# USB.net
KiCad netlist of a schematic drawn in Altium Designer
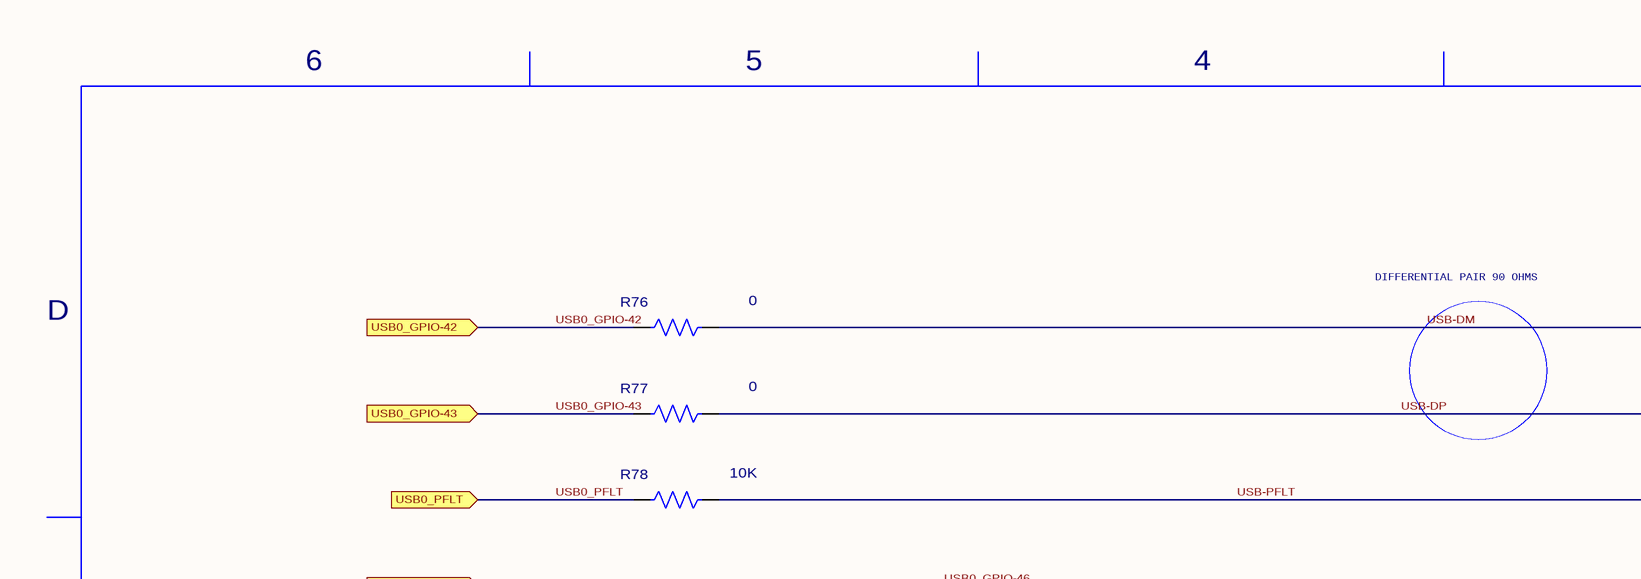
[diagram p0: USB.SchDoc, top left]
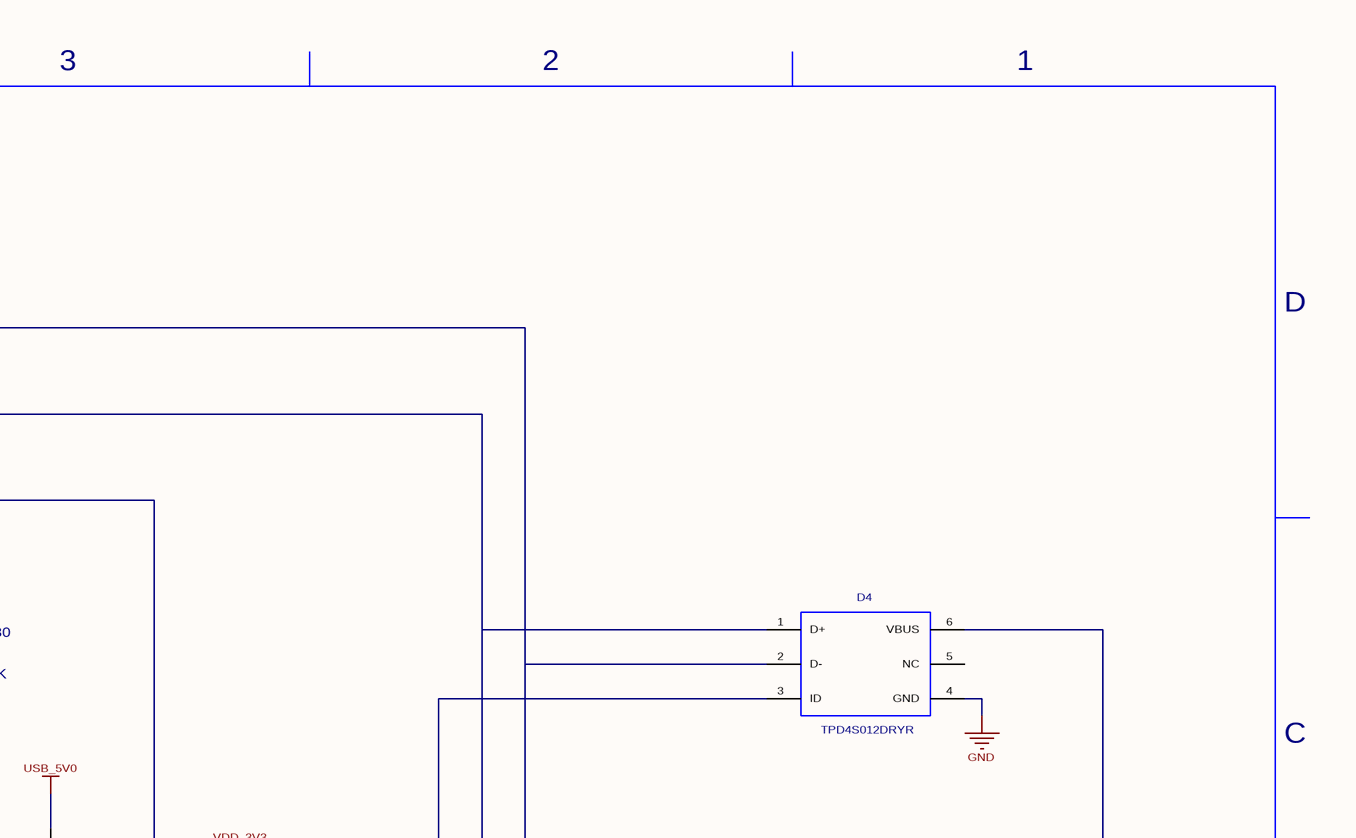
[diagram p1: USB.SchDoc, top right]
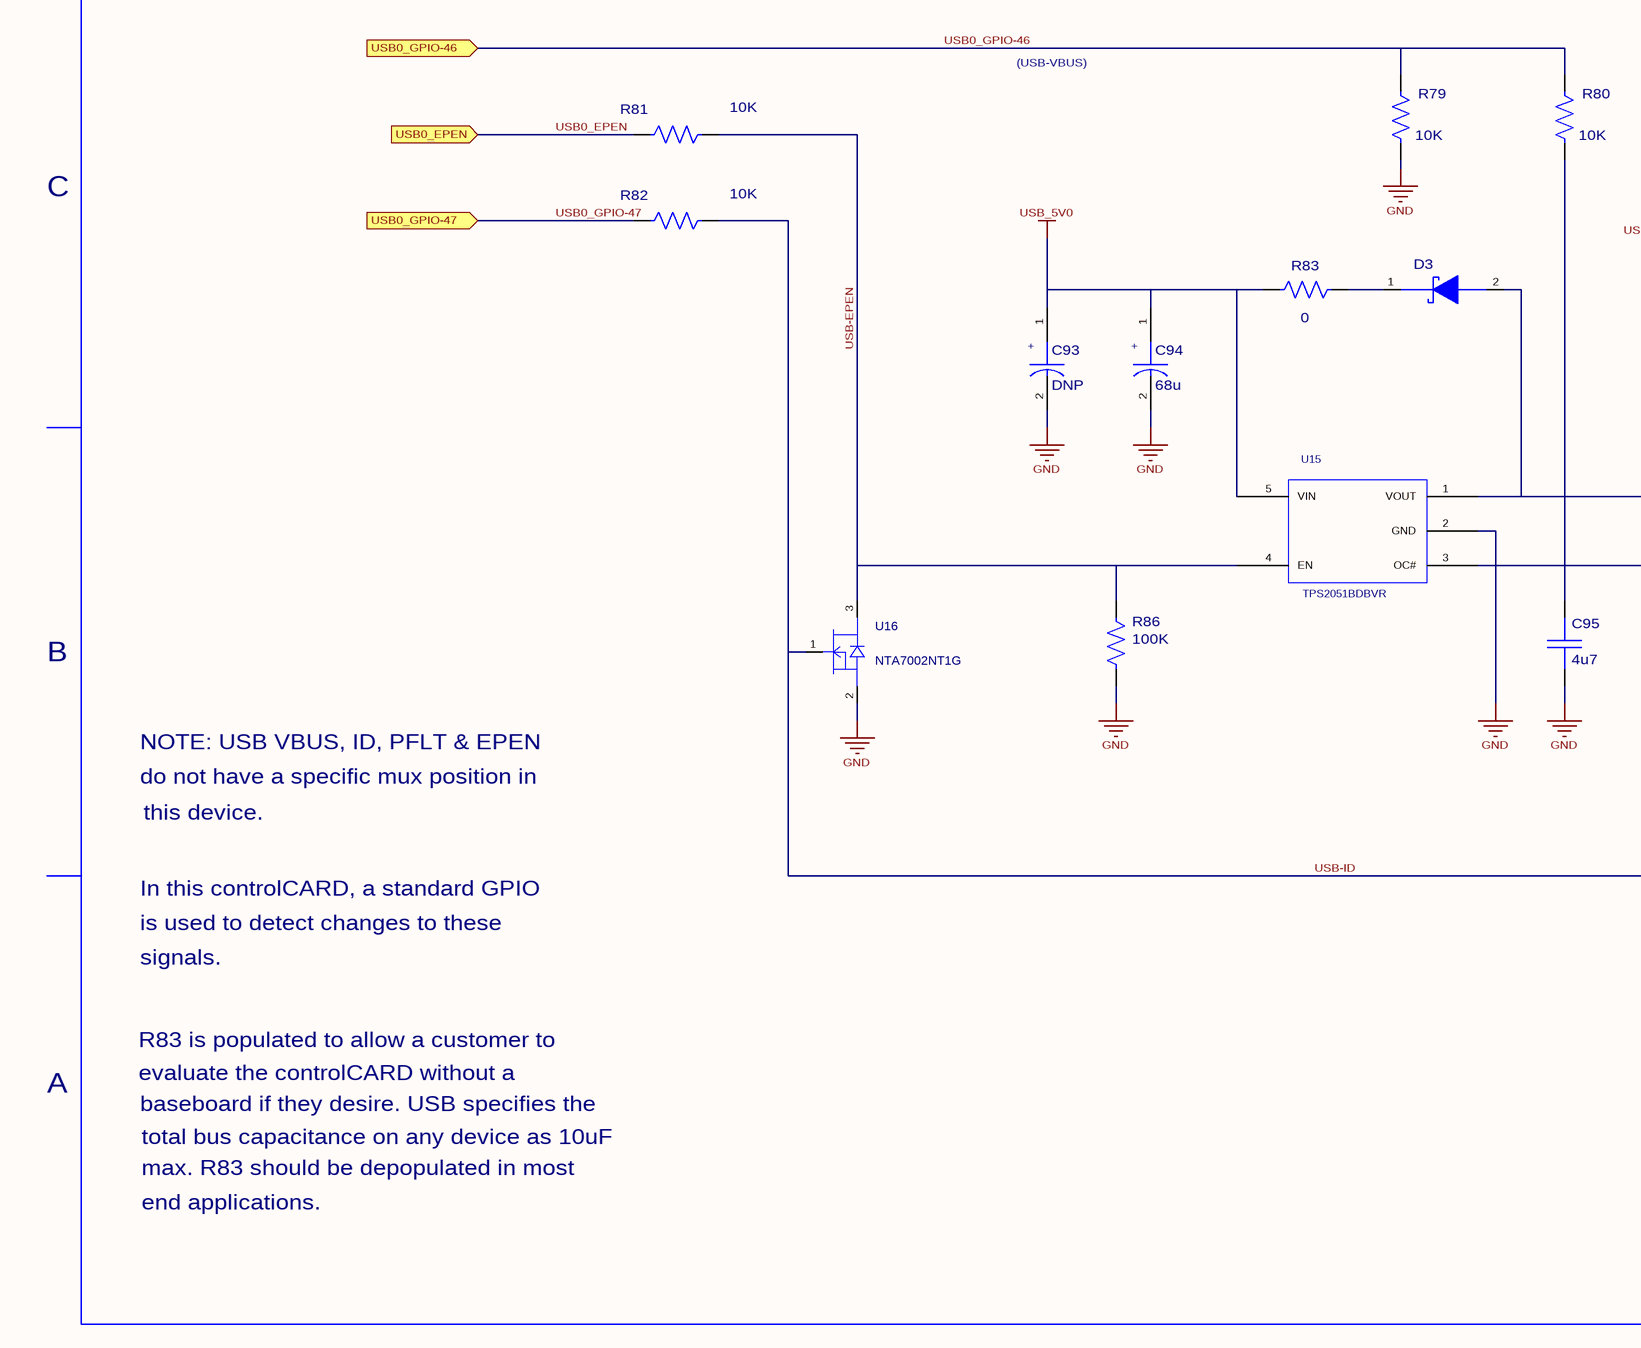
[diagram p2: USB.SchDoc, bottom left]
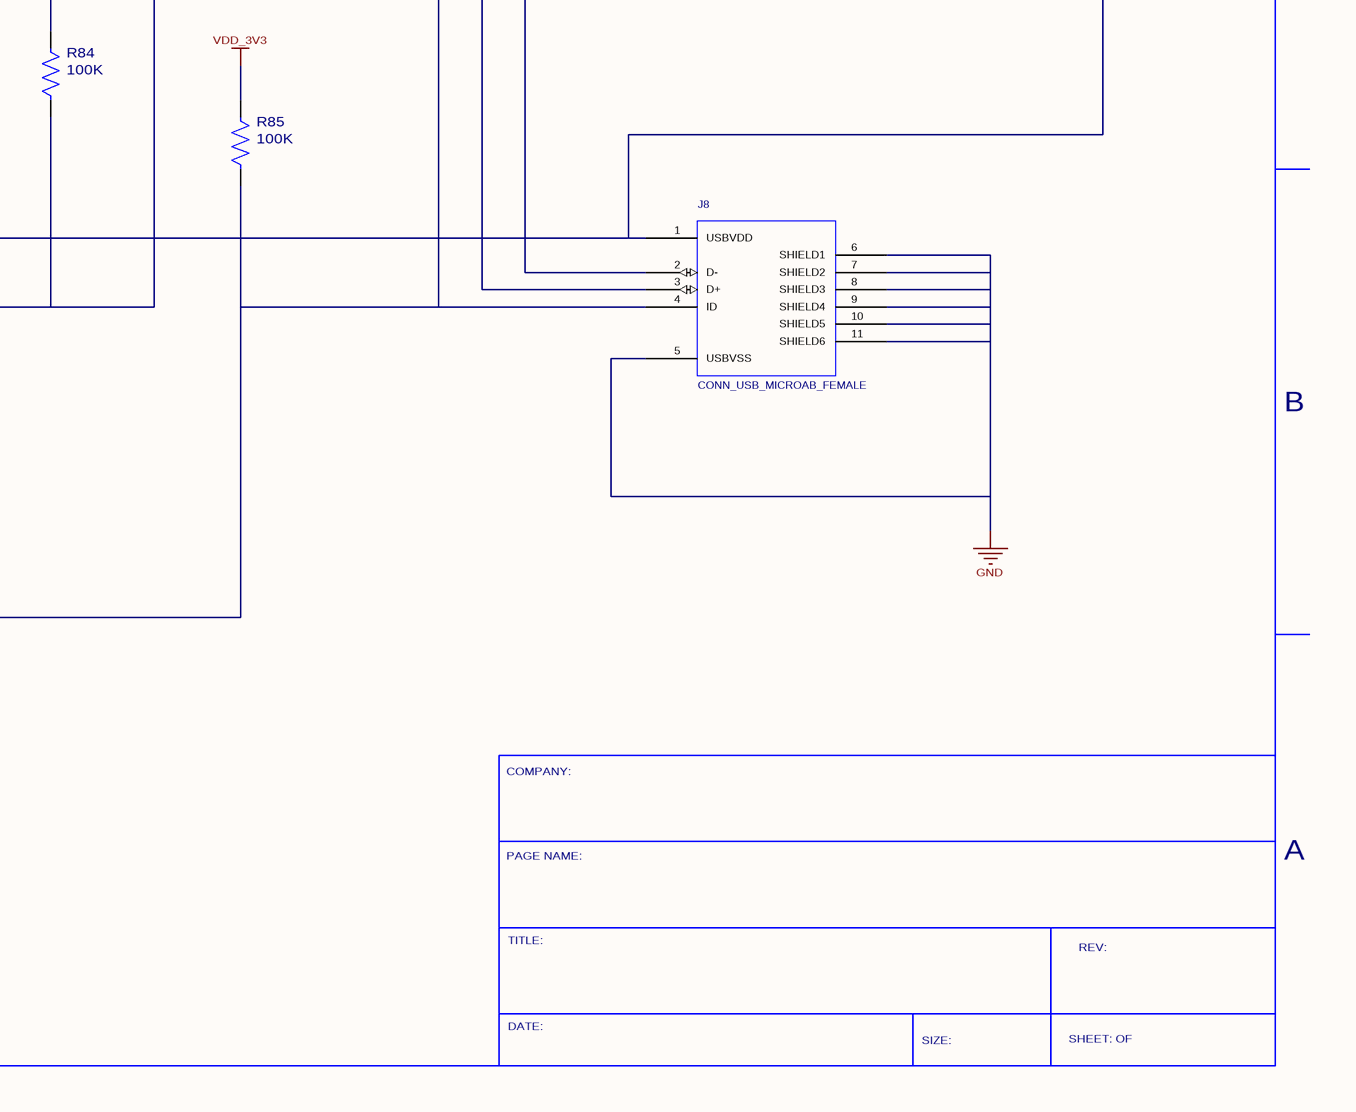
[diagram p3: USB.SchDoc, bottom right]

(export (version "E")
  (design (tool "Eeschema 10.0.6"))
  (components
    (comp (ref "C93")
      (value "DNP")
      (footprint "C1206P")
      (description "CAP TANT 20% 1206")
      (fields (field (name "Comment") "C1206_10V_TANT"))
      (libsource (lib "*") (part "C1206_10V_TANT"))
    )
    (comp (ref "C94")
      (value "68u")
      (footprint "C1206P")
      (description "CAP TANT 10V 20% 1206")
      (fields (field (name "PART NUMBER") "TLJA686M010R1500") (field (name "Comment") "C1206_10V_TANT"))
      (libsource (lib "*") (part "C1206_10V_TANT"))
    )
    (comp (ref "C95")
      (value "4u7")
      (footprint "C0603")
      (description "CAP CER 6.3V 10% X5R 0603")
      (fields (field (name "Comment") "C0603_16V_X7R"))
      (libsource (lib "*") (part "C0603_16V_X7R"))
    )
    (comp (ref "D3")
      (value "DIODE_SCHOTTKY_MBRM110ET1G")
      (footprint "DO-216AA")
      (description "DIODE SCHOTTKY 10V 1A POWERMITE")
      (fields (field (name "PART NUMBER") "MBRM110ET1G") (field (name "MANUFACTURER") "On Semiconductor"))
      (libsource (lib "*") (part "DIODE_SCHOTTKY_MBRM110ET1G"))
    )
    (comp (ref "D4")
      (value "DIODE_USBOTG_TPD4S012DRY")
      (footprint "TI_DRY_6_(R-PUSON-N6)")
      (description "4-channel USB ESD Diode for USB-HS/USB OTG; 6SON")
      (fields (field (name "MANUFACTURER") "Texas Instruments") (field (name "PART NUMBER") "TPD4S012DRYR"))
      (libsource (lib "*") (part "DIODE_USBOTG_TPD4S012DRY"))
    )
    (comp (ref "J8")
      (value "CONN_USB_MICROAB_FEMALE")
      (footprint "CONN_USB_MICROAB_FEMALE")
      (description "USB micro AB Female USB2.0")
      (fields (field (name "MANUFACTURER") "TE Connectivity") (field (name "PART NUMBER") "1981584-1"))
      (libsource (lib "*") (part "CONN_USB_MICROAB_FEMALE"))
    )
    (comp (ref "R76")
      (value "0")
      (footprint "R0402")
      (description "RES 1/16W 5% 0402 SMD")
      (fields (field (name "Comment") "R0402_5%"))
      (libsource (lib "*") (part "R0402_5%"))
    )
    (comp (ref "R77")
      (value "0")
      (footprint "R0402")
      (description "RES 1/16W 5% 0402 SMD")
      (fields (field (name "Comment") "R0402_5%"))
      (libsource (lib "*") (part "R0402_5%"))
    )
    (comp (ref "R78")
      (value "10K")
      (footprint "R0402")
      (description "RES 1/16W 5% 0402 SMD")
      (fields (field (name "Comment") "R0402_5%"))
      (libsource (lib "*") (part "R0402_5%"))
    )
    (comp (ref "R79")
      (value "10K")
      (footprint "R0402")
      (description "RES 1/16W 5% 0402 SMD")
      (fields (field (name "Comment") "R0402_5%"))
      (libsource (lib "*") (part "R0402_5%"))
    )
    (comp (ref "R80")
      (value "10K")
      (footprint "R0402")
      (description "RES 1/16W 5% 0402 SMD")
      (fields (field (name "Comment") "R0402_5%"))
      (libsource (lib "*") (part "R0402_5%"))
    )
    (comp (ref "R81")
      (value "10K")
      (footprint "R0402")
      (description "RES 1/16W 5% 0402 SMD")
      (fields (field (name "Comment") "R0402_5%"))
      (libsource (lib "*") (part "R0402_5%"))
    )
    (comp (ref "R82")
      (value "10K")
      (footprint "R0402")
      (description "RES 1/16W 5% 0402 SMD")
      (fields (field (name "Comment") "R0402_5%"))
      (libsource (lib "*") (part "R0402_5%"))
    )
    (comp (ref "R83")
      (value "0")
      (footprint "R0603")
      (description "RES 1/10W 5% 0603 SMD")
      (fields (field (name "Comment") "R0603_5%"))
      (libsource (lib "*") (part "R0603_5%"))
    )
    (comp (ref "R84")
      (value "100K")
      (footprint "R0603")
      (description "RES 1/10W 5% 0603 SMD")
      (fields (field (name "Comment") "R0603_5%"))
      (libsource (lib "*") (part "R0603_5%"))
    )
    (comp (ref "R85")
      (value "100K")
      (footprint "R0603")
      (description "RES 1/10W 5% 0603 SMD")
      (fields (field (name "Comment") "R0603_5%"))
      (libsource (lib "*") (part "R0603_5%"))
    )
    (comp (ref "R86")
      (value "100K")
      (footprint "R0603")
      (description "RES 1/10W 5% 0603 SMD")
      (fields (field (name "Comment") "R0603_5%"))
      (libsource (lib "*") (part "R0603_5%"))
    )
    (comp (ref "U15")
      (value "TPS2051BDBVR")
      (footprint "SOT-23-5")
      (description "High-Side Power Distribution Switch")
      (fields (field (name "MANUFACTURER") "Texas Instruments") (field (name "Comment") "IC_TPS2051BDBVR"))
      (libsource (lib "*") (part "IC_TPS2051BDBVR"))
    )
    (comp (ref "U16")
      (value "NTA7002NT1G")
      (footprint "SC-75")
      (description "N-channel MOSFET 30V 0.154A")
      (fields
        (field (name "MANUFACTURER") "On Semiconductor")
        (field (name "Comment") "MOSFET_30V_0.154A_NTA7002NT1G")
      )
      (libsource (lib "*") (part "MOSFET_30V_0.154A_NTA7002NT1G"))
    )
  )
  (nets
    (net (code "1") (name "/USB-DM") (class "Default")
      (node (ref "D4") (pin "2") (pinfunction "D-_2") (pintype "power_in"))
      (node (ref "J8") (pin "2") (pinfunction "D-_2") (pintype "bidirectional"))
      (node (ref "R76") (pin "2") (pinfunction "2_2") (pintype "passive"))
    )
    (net (code "2") (name "/USB-DP") (class "Default")
      (node (ref "D4") (pin "1") (pinfunction "D+_1") (pintype "passive"))
      (node (ref "J8") (pin "3") (pinfunction "D+_3") (pintype "bidirectional"))
      (node (ref "R77") (pin "2") (pinfunction "2_2") (pintype "passive"))
    )
    (net (code "3") (name "/USB-EPEN") (class "Default")
      (node (ref "R81") (pin "2") (pinfunction "2_2") (pintype "passive"))
      (node (ref "R86") (pin "1") (pinfunction "1_1") (pintype "passive"))
      (node (ref "U15") (pin "4") (pinfunction "EN_4") (pintype "passive"))
      (node (ref "U16") (pin "3") (pinfunction "S_3") (pintype "passive"))
    )
    (net (code "4") (name "/USB-ID") (class "Default")
      (node (ref "D4") (pin "3") (pinfunction "ID_3") (pintype "passive"))
      (node (ref "J8") (pin "4") (pinfunction "ID_4") (pintype "passive"))
      (node (ref "R82") (pin "2") (pinfunction "2_2") (pintype "passive"))
      (node (ref "R85") (pin "2") (pinfunction "2_2") (pintype "passive"))
      (node (ref "U16") (pin "1") (pinfunction "G_1") (pintype "passive"))
    )
    (net (code "5") (name "/USB-PFLT") (class "Default")
      (node (ref "R78") (pin "2") (pinfunction "2_2") (pintype "passive"))
      (node (ref "R84") (pin "2") (pinfunction "2_2") (pintype "passive"))
      (node (ref "U15") (pin "3") (pinfunction "OC#_3") (pintype "passive"))
    )
    (net (code "6") (name "/USB0_EPEN") (class "Default")
      (node (ref "R81") (pin "1") (pinfunction "1_1") (pintype "passive"))
    )
    (net (code "7") (name "/USB0_GPIO-42") (class "Default")
      (node (ref "R76") (pin "1") (pinfunction "1_1") (pintype "passive"))
    )
    (net (code "8") (name "/USB0_GPIO-43") (class "Default")
      (node (ref "R77") (pin "1") (pinfunction "1_1") (pintype "passive"))
    )
    (net (code "9") (name "/USB0_GPIO-46") (class "Default")
      (node (ref "R79") (pin "1") (pinfunction "1_1") (pintype "passive"))
      (node (ref "R80") (pin "1") (pinfunction "1_1") (pintype "passive"))
    )
    (net (code "10") (name "/USB0_GPIO-47") (class "Default")
      (node (ref "R82") (pin "1") (pinfunction "1_1") (pintype "passive"))
    )
    (net (code "11") (name "/USB0_PFLT") (class "Default")
      (node (ref "R78") (pin "1") (pinfunction "1_1") (pintype "passive"))
    )
    (net (code "12") (name "GND") (class "Default")
      (node (ref "C93") (pin "2") (pinfunction "2_2") (pintype "passive"))
      (node (ref "C94") (pin "2") (pinfunction "2_2") (pintype "passive"))
      (node (ref "C95") (pin "1") (pinfunction "1_1") (pintype "passive"))
      (node (ref "D4") (pin "4") (pinfunction "GND_4") (pintype "passive"))
      (node (ref "J8") (pin "10") (pinfunction "SHIELD5_10") (pintype "passive"))
      (node (ref "J8") (pin "11") (pinfunction "SHIELD6_11") (pintype "passive"))
      (node (ref "J8") (pin "5") (pinfunction "USBVSS_5") (pintype "power_in"))
      (node (ref "J8") (pin "6") (pinfunction "SHIELD1_6") (pintype "passive"))
      (node (ref "J8") (pin "7") (pinfunction "SHIELD2_7") (pintype "passive"))
      (node (ref "J8") (pin "8") (pinfunction "SHIELD3_8") (pintype "passive"))
      (node (ref "J8") (pin "9") (pinfunction "SHIELD4_9") (pintype "passive"))
      (node (ref "R79") (pin "2") (pinfunction "2_2") (pintype "passive"))
      (node (ref "R86") (pin "2") (pinfunction "2_2") (pintype "passive"))
      (node (ref "U15") (pin "2") (pinfunction "GND_2") (pintype "passive"))
      (node (ref "U16") (pin "2") (pinfunction "D_2") (pintype "passive"))
    )
    (net (code "13") (name "Net-(D3-A)") (class "Default")
      (node (ref "C95") (pin "2") (pinfunction "2_2") (pintype "passive"))
      (node (ref "D3") (pin "2") (pinfunction "A_2") (pintype "passive"))
      (node (ref "D4") (pin "6") (pinfunction "VBUS_6") (pintype "passive"))
      (node (ref "J8") (pin "1") (pinfunction "USBVDD_1") (pintype "power_in"))
      (node (ref "R80") (pin "2") (pinfunction "2_2") (pintype "passive"))
      (node (ref "U15") (pin "1") (pinfunction "VOUT_1") (pintype "passive"))
    )
    (net (code "14") (name "Net-(D3-C)") (class "Default")
      (node (ref "D3") (pin "1") (pinfunction "C_1") (pintype "passive"))
      (node (ref "R83") (pin "2") (pinfunction "2_2") (pintype "passive"))
    )
    (net (code "15") (name "USB_5V0") (class "Default")
      (node (ref "C93") (pin "1") (pinfunction "1_1") (pintype "passive"))
      (node (ref "C94") (pin "1") (pinfunction "1_1") (pintype "passive"))
      (node (ref "R83") (pin "1") (pinfunction "1_1") (pintype "passive"))
      (node (ref "R84") (pin "1") (pinfunction "1_1") (pintype "passive"))
      (node (ref "U15") (pin "5") (pinfunction "VIN_5") (pintype "passive"))
    )
    (net (code "16") (name "VDD_3V3") (class "Default")
      (node (ref "R85") (pin "1") (pinfunction "1_1") (pintype "passive"))
    )
    (net (code "17") (name "unconnected-(D4-NC-Pad5)") (class "Default")
      (node (ref "D4") (pin "5") (pinfunction "NC_5") (pintype "passive"))
    )
  )
)
